# UI.net
KiCad netlist of a schematic drawn in Altium Designer
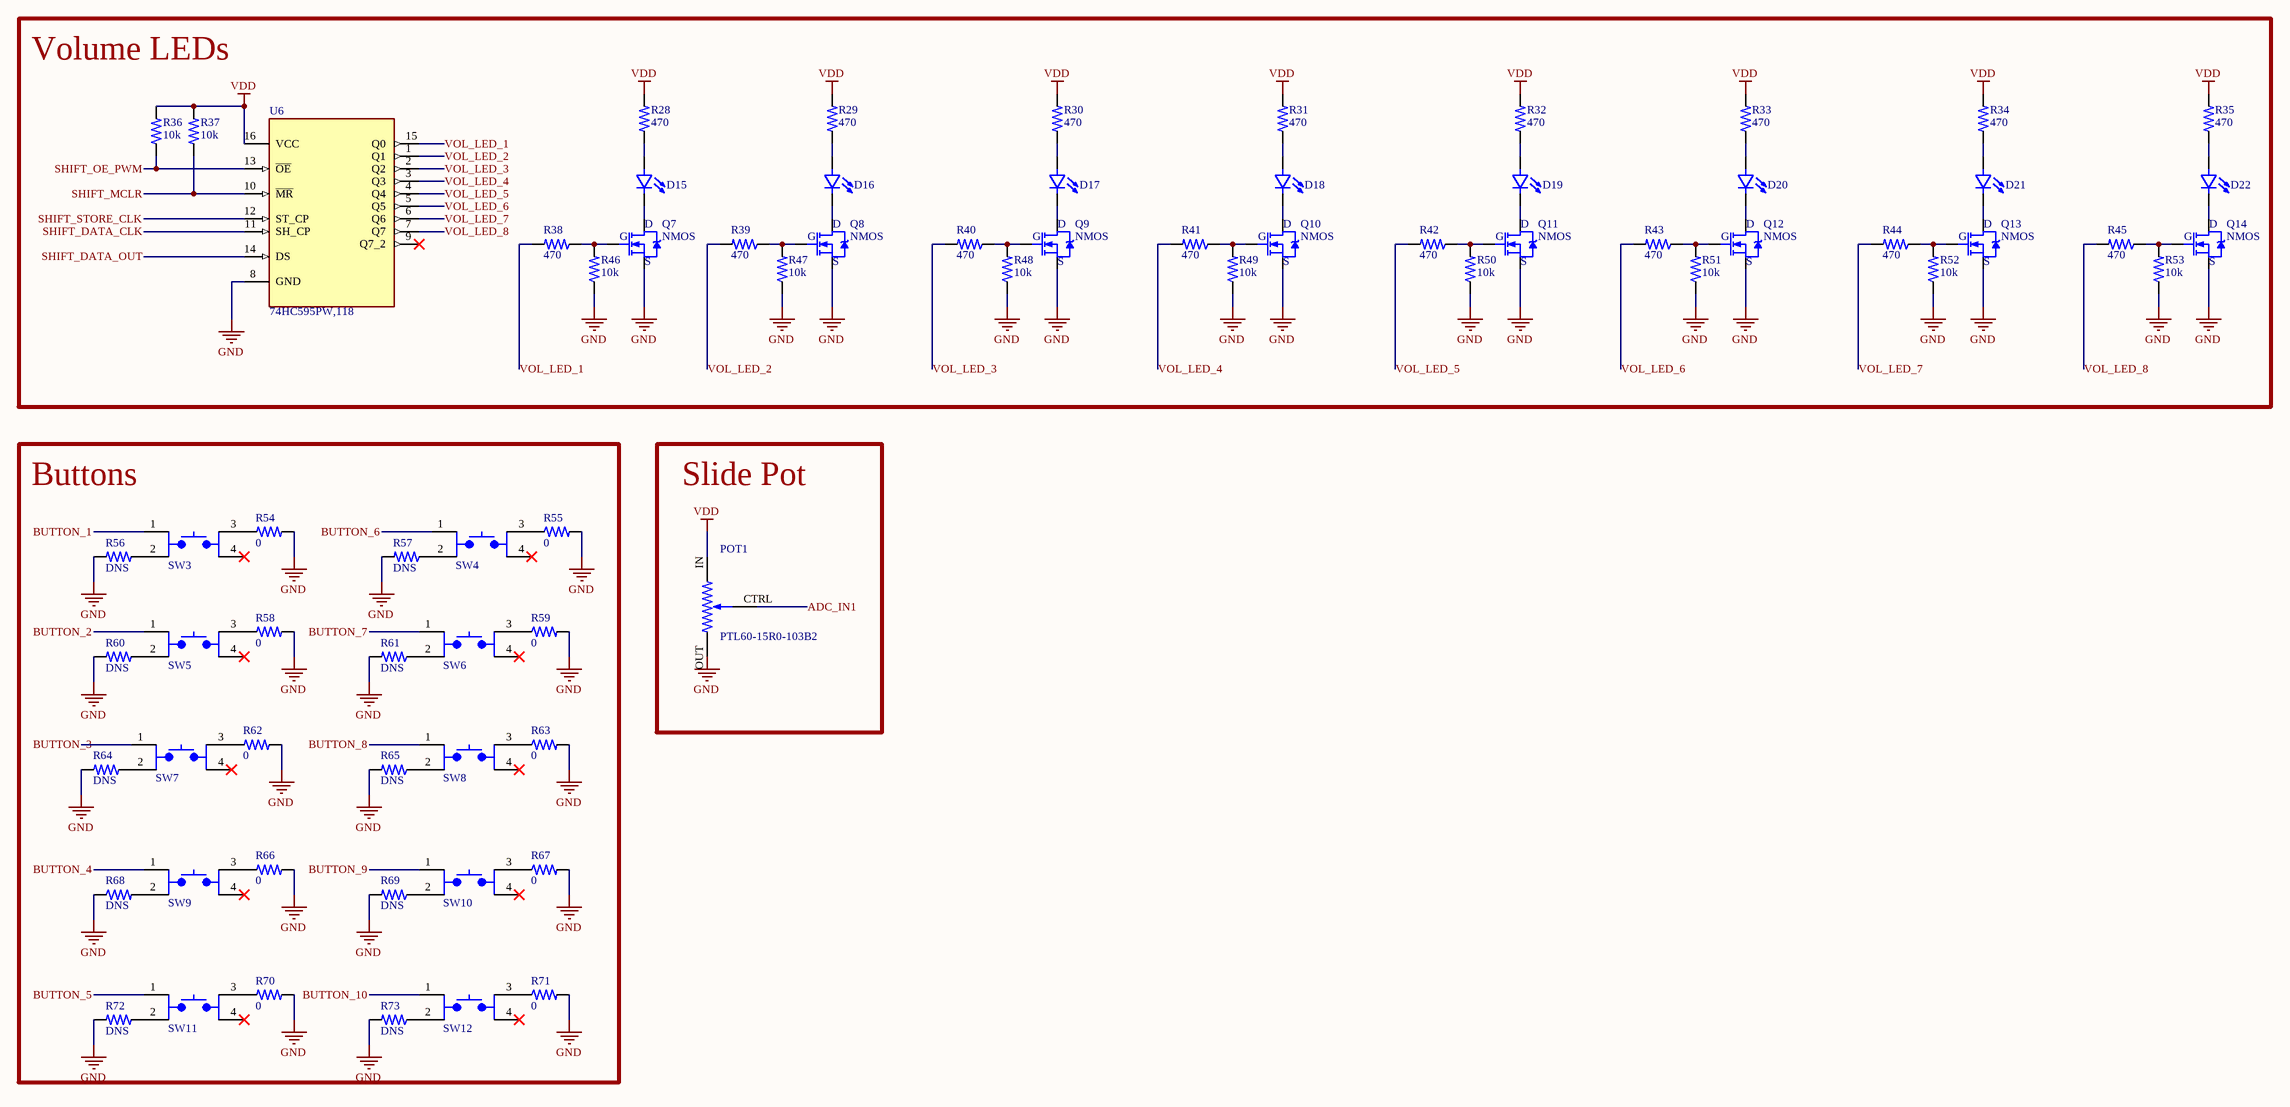
[diagram p0: UI.SchDoc]

(export (version "E")
  (design (tool "Eeschema 10.0.6"))
  (components
    (comp (ref "D15")
      (value "LED - single")
      (footprint "Christmas-2023_Soundboard:0603-LED")
      (description "LED")
      (fields (field (name "MFR") "Everlight Elec"))
      (libsource (lib "Christmas-2023_Soundboard") (part "LED - single"))
    )
    (comp (ref "D16")
      (value "LED - single")
      (footprint "Christmas-2023_Soundboard:0603-LED")
      (description "LED")
      (fields (field (name "MFR") "Hubei KENTO Elec"))
      (libsource (lib "Christmas-2023_Soundboard") (part "LED - single"))
    )
    (comp (ref "D17")
      (value "LED - single")
      (footprint "Christmas-2023_Soundboard:0603-LED")
      (description "LED")
      (fields (field (name "MFR") "Everlight Elec"))
      (libsource (lib "Christmas-2023_Soundboard") (part "LED - single"))
    )
    (comp (ref "D18")
      (value "LED - single")
      (footprint "Christmas-2023_Soundboard:0603-LED")
      (description "LED")
      (fields (field (name "MFR") "Hubei KENTO Elec"))
      (libsource (lib "Christmas-2023_Soundboard") (part "LED - single"))
    )
    (comp (ref "D19")
      (value "LED - single")
      (footprint "Christmas-2023_Soundboard:0603-LED")
      (description "LED")
      (fields (field (name "MFR") "Everlight Elec"))
      (libsource (lib "Christmas-2023_Soundboard") (part "LED - single"))
    )
    (comp (ref "D20")
      (value "LED - single")
      (footprint "Christmas-2023_Soundboard:0603-LED")
      (description "LED")
      (fields (field (name "MFR") "Hubei KENTO Elec"))
      (libsource (lib "Christmas-2023_Soundboard") (part "LED - single"))
    )
    (comp (ref "D21")
      (value "LED - single")
      (footprint "Christmas-2023_Soundboard:0603-LED")
      (description "LED")
      (fields (field (name "MFR") "Everlight Elec"))
      (libsource (lib "Christmas-2023_Soundboard") (part "LED - single"))
    )
    (comp (ref "D22")
      (value "LED - single")
      (footprint "Christmas-2023_Soundboard:0603-LED")
      (description "LED")
      (fields (field (name "MFR") "Hubei KENTO Elec"))
      (libsource (lib "Christmas-2023_Soundboard") (part "LED - single"))
    )
    (comp (ref "POT1")
      (value "PTL60-15R0-103B2")
      (footprint "Christmas-2023_Soundboard:BIG SLIDE POT")
      (description "POT 470 OHM 1/10W CARBON LINEAR")
      (fields (field (name "MFR") "Bourns Inc."))
      (libsource (lib "Christmas-2023_Soundboard") (part "POT"))
    )
    (comp (ref "Q7")
      (value "NMOS")
      (footprint "Christmas-2023_Soundboard:SOT-23")
      (description "N-Channel MOSFET")
      (fields (field (name "MFR") "Diodes Incorporated"))
      (libsource (lib "Christmas-2023_Soundboard") (part "NMOS"))
    )
    (comp (ref "Q8")
      (value "NMOS")
      (footprint "Christmas-2023_Soundboard:SOT-23")
      (description "N-Channel MOSFET")
      (fields (field (name "MFR") "Diodes Incorporated"))
      (libsource (lib "Christmas-2023_Soundboard") (part "NMOS"))
    )
    (comp (ref "Q9")
      (value "NMOS")
      (footprint "Christmas-2023_Soundboard:SOT-23")
      (description "N-Channel MOSFET")
      (fields (field (name "MFR") "Diodes Incorporated"))
      (libsource (lib "Christmas-2023_Soundboard") (part "NMOS"))
    )
    (comp (ref "Q10")
      (value "NMOS")
      (footprint "Christmas-2023_Soundboard:SOT-23")
      (description "N-Channel MOSFET")
      (fields (field (name "MFR") "Diodes Incorporated"))
      (libsource (lib "Christmas-2023_Soundboard") (part "NMOS"))
    )
    (comp (ref "Q11")
      (value "NMOS")
      (footprint "Christmas-2023_Soundboard:SOT-23")
      (description "N-Channel MOSFET")
      (fields (field (name "MFR") "Diodes Incorporated"))
      (libsource (lib "Christmas-2023_Soundboard") (part "NMOS"))
    )
    (comp (ref "Q12")
      (value "NMOS")
      (footprint "Christmas-2023_Soundboard:SOT-23")
      (description "N-Channel MOSFET")
      (fields (field (name "MFR") "Diodes Incorporated"))
      (libsource (lib "Christmas-2023_Soundboard") (part "NMOS"))
    )
    (comp (ref "Q13")
      (value "NMOS")
      (footprint "Christmas-2023_Soundboard:SOT-23")
      (description "N-Channel MOSFET")
      (fields (field (name "MFR") "Diodes Incorporated"))
      (libsource (lib "Christmas-2023_Soundboard") (part "NMOS"))
    )
    (comp (ref "Q14")
      (value "NMOS")
      (footprint "Christmas-2023_Soundboard:SOT-23")
      (description "N-Channel MOSFET")
      (fields (field (name "MFR") "Diodes Incorporated"))
      (libsource (lib "Christmas-2023_Soundboard") (part "NMOS"))
    )
    (comp (ref "R28")
      (value "470")
      (footprint "Christmas-2023_Soundboard:0603-RES")
      (description "Resistor")
      (fields (field (name "Comment") "RES"))
      (libsource (lib "Christmas-2023_Soundboard") (part "RES"))
    )
    (comp (ref "R29")
      (value "470")
      (footprint "Christmas-2023_Soundboard:0603-RES")
      (description "Resistor")
      (fields (field (name "Comment") "RES"))
      (libsource (lib "Christmas-2023_Soundboard") (part "RES"))
    )
    (comp (ref "R30")
      (value "470")
      (footprint "Christmas-2023_Soundboard:0603-RES")
      (description "Resistor")
      (fields (field (name "Comment") "RES"))
      (libsource (lib "Christmas-2023_Soundboard") (part "RES"))
    )
    (comp (ref "R31")
      (value "470")
      (footprint "Christmas-2023_Soundboard:0603-RES")
      (description "Resistor")
      (fields (field (name "Comment") "RES"))
      (libsource (lib "Christmas-2023_Soundboard") (part "RES"))
    )
    (comp (ref "R32")
      (value "470")
      (footprint "Christmas-2023_Soundboard:0603-RES")
      (description "Resistor")
      (fields (field (name "Comment") "RES"))
      (libsource (lib "Christmas-2023_Soundboard") (part "RES"))
    )
    (comp (ref "R33")
      (value "470")
      (footprint "Christmas-2023_Soundboard:0603-RES")
      (description "Resistor")
      (fields (field (name "Comment") "RES"))
      (libsource (lib "Christmas-2023_Soundboard") (part "RES"))
    )
    (comp (ref "R34")
      (value "470")
      (footprint "Christmas-2023_Soundboard:0603-RES")
      (description "Resistor")
      (fields (field (name "Comment") "RES"))
      (libsource (lib "Christmas-2023_Soundboard") (part "RES"))
    )
    (comp (ref "R35")
      (value "470")
      (footprint "Christmas-2023_Soundboard:0603-RES")
      (description "Resistor")
      (fields (field (name "Comment") "RES"))
      (libsource (lib "Christmas-2023_Soundboard") (part "RES"))
    )
    (comp (ref "R36")
      (value "10k")
      (footprint "Christmas-2023_Soundboard:0603-RES")
      (description "Resistor")
      (fields (field (name "Comment") "RES"))
      (libsource (lib "Christmas-2023_Soundboard") (part "RES"))
    )
    (comp (ref "R37")
      (value "10k")
      (footprint "Christmas-2023_Soundboard:0603-RES")
      (description "Resistor")
      (fields (field (name "Comment") "RES"))
      (libsource (lib "Christmas-2023_Soundboard") (part "RES"))
    )
    (comp (ref "R38")
      (value "470")
      (footprint "Christmas-2023_Soundboard:0603-RES")
      (description "Resistor")
      (fields (field (name "Comment") "RES"))
      (libsource (lib "Christmas-2023_Soundboard") (part "RES"))
    )
    (comp (ref "R39")
      (value "470")
      (footprint "Christmas-2023_Soundboard:0603-RES")
      (description "Resistor")
      (fields (field (name "Comment") "RES"))
      (libsource (lib "Christmas-2023_Soundboard") (part "RES"))
    )
    (comp (ref "R40")
      (value "470")
      (footprint "Christmas-2023_Soundboard:0603-RES")
      (description "Resistor")
      (fields (field (name "Comment") "RES"))
      (libsource (lib "Christmas-2023_Soundboard") (part "RES"))
    )
    (comp (ref "R41")
      (value "470")
      (footprint "Christmas-2023_Soundboard:0603-RES")
      (description "Resistor")
      (fields (field (name "Comment") "RES"))
      (libsource (lib "Christmas-2023_Soundboard") (part "RES"))
    )
    (comp (ref "R42")
      (value "470")
      (footprint "Christmas-2023_Soundboard:0603-RES")
      (description "Resistor")
      (fields (field (name "Comment") "RES"))
      (libsource (lib "Christmas-2023_Soundboard") (part "RES"))
    )
    (comp (ref "R43")
      (value "470")
      (footprint "Christmas-2023_Soundboard:0603-RES")
      (description "Resistor")
      (fields (field (name "Comment") "RES"))
      (libsource (lib "Christmas-2023_Soundboard") (part "RES"))
    )
    (comp (ref "R44")
      (value "470")
      (footprint "Christmas-2023_Soundboard:0603-RES")
      (description "Resistor")
      (fields (field (name "Comment") "RES"))
      (libsource (lib "Christmas-2023_Soundboard") (part "RES"))
    )
    (comp (ref "R45")
      (value "470")
      (footprint "Christmas-2023_Soundboard:0603-RES")
      (description "Resistor")
      (fields (field (name "Comment") "RES"))
      (libsource (lib "Christmas-2023_Soundboard") (part "RES"))
    )
    (comp (ref "R46")
      (value "10k")
      (footprint "Christmas-2023_Soundboard:0603-RES")
      (description "Resistor")
      (fields (field (name "Comment") "RES"))
      (libsource (lib "Christmas-2023_Soundboard") (part "RES"))
    )
    (comp (ref "R47")
      (value "10k")
      (footprint "Christmas-2023_Soundboard:0603-RES")
      (description "Resistor")
      (fields (field (name "Comment") "RES"))
      (libsource (lib "Christmas-2023_Soundboard") (part "RES"))
    )
    (comp (ref "R48")
      (value "10k")
      (footprint "Christmas-2023_Soundboard:0603-RES")
      (description "Resistor")
      (fields (field (name "Comment") "RES"))
      (libsource (lib "Christmas-2023_Soundboard") (part "RES"))
    )
    (comp (ref "R49")
      (value "10k")
      (footprint "Christmas-2023_Soundboard:0603-RES")
      (description "Resistor")
      (fields (field (name "Comment") "RES"))
      (libsource (lib "Christmas-2023_Soundboard") (part "RES"))
    )
    (comp (ref "R50")
      (value "10k")
      (footprint "Christmas-2023_Soundboard:0603-RES")
      (description "Resistor")
      (fields (field (name "Comment") "RES"))
      (libsource (lib "Christmas-2023_Soundboard") (part "RES"))
    )
    (comp (ref "R51")
      (value "10k")
      (footprint "Christmas-2023_Soundboard:0603-RES")
      (description "Resistor")
      (fields (field (name "Comment") "RES"))
      (libsource (lib "Christmas-2023_Soundboard") (part "RES"))
    )
    (comp (ref "R52")
      (value "10k")
      (footprint "Christmas-2023_Soundboard:0603-RES")
      (description "Resistor")
      (fields (field (name "Comment") "RES"))
      (libsource (lib "Christmas-2023_Soundboard") (part "RES"))
    )
    (comp (ref "R53")
      (value "10k")
      (footprint "Christmas-2023_Soundboard:0603-RES")
      (description "Resistor")
      (fields (field (name "Comment") "RES"))
      (libsource (lib "Christmas-2023_Soundboard") (part "RES"))
    )
    (comp (ref "R54")
      (value "0")
      (footprint "Christmas-2023_Soundboard:0603-RES")
      (description "Resistor")
      (fields (field (name "Comment") "RES"))
      (libsource (lib "Christmas-2023_Soundboard") (part "RES"))
    )
    (comp (ref "R55")
      (value "0")
      (footprint "Christmas-2023_Soundboard:0603-RES")
      (description "Resistor")
      (fields (field (name "Comment") "RES"))
      (libsource (lib "Christmas-2023_Soundboard") (part "RES"))
    )
    (comp (ref "R56")
      (value "DNS")
      (footprint "Christmas-2023_Soundboard:0603-RES")
      (description "Resistor")
      (fields (field (name "Comment") "RES"))
      (libsource (lib "Christmas-2023_Soundboard") (part "RES"))
    )
    (comp (ref "R57")
      (value "DNS")
      (footprint "Christmas-2023_Soundboard:0603-RES")
      (description "Resistor")
      (fields (field (name "Comment") "RES"))
      (libsource (lib "Christmas-2023_Soundboard") (part "RES"))
    )
    (comp (ref "R58")
      (value "0")
      (footprint "Christmas-2023_Soundboard:0603-RES")
      (description "Resistor")
      (fields (field (name "Comment") "RES"))
      (libsource (lib "Christmas-2023_Soundboard") (part "RES"))
    )
    (comp (ref "R59")
      (value "0")
      (footprint "Christmas-2023_Soundboard:0603-RES")
      (description "Resistor")
      (fields (field (name "Comment") "RES"))
      (libsource (lib "Christmas-2023_Soundboard") (part "RES"))
    )
    (comp (ref "R60")
      (value "DNS")
      (footprint "Christmas-2023_Soundboard:0603-RES")
      (description "Resistor")
      (fields (field (name "Comment") "RES"))
      (libsource (lib "Christmas-2023_Soundboard") (part "RES"))
    )
    (comp (ref "R61")
      (value "DNS")
      (footprint "Christmas-2023_Soundboard:0603-RES")
      (description "Resistor")
      (fields (field (name "Comment") "RES"))
      (libsource (lib "Christmas-2023_Soundboard") (part "RES"))
    )
    (comp (ref "R62")
      (value "0")
      (footprint "Christmas-2023_Soundboard:0603-RES")
      (description "Resistor")
      (fields (field (name "Comment") "RES"))
      (libsource (lib "Christmas-2023_Soundboard") (part "RES"))
    )
    (comp (ref "R63")
      (value "0")
      (footprint "Christmas-2023_Soundboard:0603-RES")
      (description "Resistor")
      (fields (field (name "Comment") "RES"))
      (libsource (lib "Christmas-2023_Soundboard") (part "RES"))
    )
    (comp (ref "R64")
      (value "DNS")
      (footprint "Christmas-2023_Soundboard:0603-RES")
      (description "Resistor")
      (fields (field (name "Comment") "RES"))
      (libsource (lib "Christmas-2023_Soundboard") (part "RES"))
    )
    (comp (ref "R65")
      (value "DNS")
      (footprint "Christmas-2023_Soundboard:0603-RES")
      (description "Resistor")
      (fields (field (name "Comment") "RES"))
      (libsource (lib "Christmas-2023_Soundboard") (part "RES"))
    )
    (comp (ref "R66")
      (value "0")
      (footprint "Christmas-2023_Soundboard:0603-RES")
      (description "Resistor")
      (fields (field (name "Comment") "RES"))
      (libsource (lib "Christmas-2023_Soundboard") (part "RES"))
    )
    (comp (ref "R67")
      (value "0")
      (footprint "Christmas-2023_Soundboard:0603-RES")
      (description "Resistor")
      (fields (field (name "Comment") "RES"))
      (libsource (lib "Christmas-2023_Soundboard") (part "RES"))
    )
    (comp (ref "R68")
      (value "DNS")
      (footprint "Christmas-2023_Soundboard:0603-RES")
      (description "Resistor")
      (fields (field (name "Comment") "RES"))
      (libsource (lib "Christmas-2023_Soundboard") (part "RES"))
    )
    (comp (ref "R69")
      (value "DNS")
      (footprint "Christmas-2023_Soundboard:0603-RES")
      (description "Resistor")
      (fields (field (name "Comment") "RES"))
      (libsource (lib "Christmas-2023_Soundboard") (part "RES"))
    )
    (comp (ref "R70")
      (value "0")
      (footprint "Christmas-2023_Soundboard:0603-RES")
      (description "Resistor")
      (fields (field (name "Comment") "RES"))
      (libsource (lib "Christmas-2023_Soundboard") (part "RES"))
    )
    (comp (ref "R71")
      (value "0")
      (footprint "Christmas-2023_Soundboard:0603-RES")
      (description "Resistor")
      (fields (field (name "Comment") "RES"))
      (libsource (lib "Christmas-2023_Soundboard") (part "RES"))
    )
    (comp (ref "R72")
      (value "DNS")
      (footprint "Christmas-2023_Soundboard:0603-RES")
      (description "Resistor")
      (fields (field (name "Comment") "RES"))
      (libsource (lib "Christmas-2023_Soundboard") (part "RES"))
    )
    (comp (ref "R73")
      (value "DNS")
      (footprint "Christmas-2023_Soundboard:0603-RES")
      (description "Resistor")
      (fields (field (name "Comment") "RES"))
      (libsource (lib "Christmas-2023_Soundboard") (part "RES"))
    )
    (comp (ref "SW3")
      (value "SPDT SMT Tactile Push Button Switch")
      (footprint "Christmas-2023_Soundboard:TACTILE SWITCH")
      (fields (field (name "MFR") "TE Connectivity ALCOSWITCH Switches"))
      (libsource (lib "Christmas-2023_Soundboard") (part "SPDT SMT Tactile Push Button Switch"))
    )
    (comp (ref "SW4")
      (value "SPDT SMT Tactile Push Button Switch")
      (footprint "Christmas-2023_Soundboard:TACTILE SWITCH")
      (fields (field (name "MFR") "TE Connectivity ALCOSWITCH Switches"))
      (libsource (lib "Christmas-2023_Soundboard") (part "SPDT SMT Tactile Push Button Switch"))
    )
    (comp (ref "SW5")
      (value "SPDT SMT Tactile Push Button Switch")
      (footprint "Christmas-2023_Soundboard:TACTILE SWITCH")
      (fields (field (name "MFR") "TE Connectivity ALCOSWITCH Switches"))
      (libsource (lib "Christmas-2023_Soundboard") (part "SPDT SMT Tactile Push Button Switch"))
    )
    (comp (ref "SW6")
      (value "SPDT SMT Tactile Push Button Switch")
      (footprint "Christmas-2023_Soundboard:TACTILE SWITCH")
      (fields (field (name "MFR") "TE Connectivity ALCOSWITCH Switches"))
      (libsource (lib "Christmas-2023_Soundboard") (part "SPDT SMT Tactile Push Button Switch"))
    )
    (comp (ref "SW7")
      (value "SPDT SMT Tactile Push Button Switch")
      (footprint "Christmas-2023_Soundboard:TACTILE SWITCH")
      (fields (field (name "MFR") "TE Connectivity ALCOSWITCH Switches"))
      (libsource (lib "Christmas-2023_Soundboard") (part "SPDT SMT Tactile Push Button Switch"))
    )
    (comp (ref "SW8")
      (value "SPDT SMT Tactile Push Button Switch")
      (footprint "Christmas-2023_Soundboard:TACTILE SWITCH")
      (fields (field (name "MFR") "TE Connectivity ALCOSWITCH Switches"))
      (libsource (lib "Christmas-2023_Soundboard") (part "SPDT SMT Tactile Push Button Switch"))
    )
    (comp (ref "SW9")
      (value "SPDT SMT Tactile Push Button Switch")
      (footprint "Christmas-2023_Soundboard:TACTILE SWITCH")
      (fields (field (name "MFR") "TE Connectivity ALCOSWITCH Switches"))
      (libsource (lib "Christmas-2023_Soundboard") (part "SPDT SMT Tactile Push Button Switch"))
    )
    (comp (ref "SW10")
      (value "SPDT SMT Tactile Push Button Switch")
      (footprint "Christmas-2023_Soundboard:TACTILE SWITCH")
      (fields (field (name "MFR") "TE Connectivity ALCOSWITCH Switches"))
      (libsource (lib "Christmas-2023_Soundboard") (part "SPDT SMT Tactile Push Button Switch"))
    )
    (comp (ref "SW11")
      (value "SPDT SMT Tactile Push Button Switch")
      (footprint "Christmas-2023_Soundboard:TACTILE SWITCH")
      (fields (field (name "MFR") "TE Connectivity ALCOSWITCH Switches"))
      (libsource (lib "Christmas-2023_Soundboard") (part "SPDT SMT Tactile Push Button Switch"))
    )
    (comp (ref "SW12")
      (value "SPDT SMT Tactile Push Button Switch")
      (footprint "Christmas-2023_Soundboard:TACTILE SWITCH")
      (fields (field (name "MFR") "TE Connectivity ALCOSWITCH Switches"))
      (libsource (lib "Christmas-2023_Soundboard") (part "SPDT SMT Tactile Push Button Switch"))
    )
    (comp (ref "U6")
      (value "74HC595PW,118")
      (footprint "Christmas-2023_Soundboard:16-TSSOP")
      (description "Shift Shift Register 1 Element 8 Bit 16-TSSOP")
      (fields (field (name "MFR") "Nexperia USA Inc."))
      (libsource (lib "Christmas-2023_Soundboard") (part "SHIFT REGISTER 8 BIT"))
    )
  )
  (nets
    (net (code "1") (name "/ADC_IN1") (class "Default")
      (node (ref "POT1") (pin "CTRL") (pinfunction "WIPER_CTRL") (pintype "passive"))
    )
    (net (code "2") (name "/BUTTON_1") (class "Default")
      (node (ref "SW3") (pin "1") (pinfunction "1_1") (pintype "passive"))
    )
    (net (code "3") (name "/BUTTON_2") (class "Default")
      (node (ref "SW5") (pin "1") (pinfunction "1_1") (pintype "passive"))
    )
    (net (code "4") (name "/BUTTON_3") (class "Default")
      (node (ref "SW7") (pin "1") (pinfunction "1_1") (pintype "passive"))
    )
    (net (code "5") (name "/BUTTON_4") (class "Default")
      (node (ref "SW9") (pin "1") (pinfunction "1_1") (pintype "passive"))
    )
    (net (code "6") (name "/BUTTON_5") (class "Default")
      (node (ref "SW11") (pin "1") (pinfunction "1_1") (pintype "passive"))
    )
    (net (code "7") (name "/BUTTON_6") (class "Default")
      (node (ref "SW4") (pin "1") (pinfunction "1_1") (pintype "passive"))
    )
    (net (code "8") (name "/BUTTON_7") (class "Default")
      (node (ref "SW6") (pin "1") (pinfunction "1_1") (pintype "passive"))
    )
    (net (code "9") (name "/BUTTON_8") (class "Default")
      (node (ref "SW8") (pin "1") (pinfunction "1_1") (pintype "passive"))
    )
    (net (code "10") (name "/BUTTON_9") (class "Default")
      (node (ref "SW10") (pin "1") (pinfunction "1_1") (pintype "passive"))
    )
    (net (code "11") (name "/BUTTON_10") (class "Default")
      (node (ref "SW12") (pin "1") (pinfunction "1_1") (pintype "passive"))
    )
    (net (code "12") (name "/SHIFT_DATA_CLK") (class "Default")
      (node (ref "U6") (pin "11") (pinfunction "SH_CP_11") (pintype "input"))
    )
    (net (code "13") (name "/SHIFT_DATA_OUT") (class "Default")
      (node (ref "U6") (pin "14") (pinfunction "DS_14") (pintype "input"))
    )
    (net (code "14") (name "/SHIFT_MCLR") (class "Default")
      (node (ref "R37") (pin "1") (pinfunction "1_1") (pintype "passive"))
      (node (ref "U6") (pin "10") (pinfunction "~{MR}_10") (pintype "input"))
    )
    (net (code "15") (name "/SHIFT_OE_PWM") (class "Default")
      (node (ref "R36") (pin "1") (pinfunction "1_1") (pintype "passive"))
      (node (ref "U6") (pin "13") (pinfunction "~{OE}_13") (pintype "input"))
    )
    (net (code "16") (name "/SHIFT_STORE_CLK") (class "Default")
      (node (ref "U6") (pin "12") (pinfunction "ST_CP_12") (pintype "input"))
    )
    (net (code "17") (name "/VOL_LED_1") (class "Default")
      (node (ref "R38") (pin "2") (pinfunction "2_2") (pintype "passive"))
      (node (ref "U6") (pin "15") (pinfunction "Q0_15") (pintype "output"))
    )
    (net (code "18") (name "/VOL_LED_2") (class "Default")
      (node (ref "R39") (pin "2") (pinfunction "2_2") (pintype "passive"))
      (node (ref "U6") (pin "1") (pinfunction "Q1_1") (pintype "output"))
    )
    (net (code "19") (name "/VOL_LED_3") (class "Default")
      (node (ref "R40") (pin "2") (pinfunction "2_2") (pintype "passive"))
      (node (ref "U6") (pin "2") (pinfunction "Q2_2") (pintype "output"))
    )
    (net (code "20") (name "/VOL_LED_4") (class "Default")
      (node (ref "R41") (pin "2") (pinfunction "2_2") (pintype "passive"))
      (node (ref "U6") (pin "3") (pinfunction "Q3_3") (pintype "output"))
    )
    (net (code "21") (name "/VOL_LED_5") (class "Default")
      (node (ref "R42") (pin "2") (pinfunction "2_2") (pintype "passive"))
      (node (ref "U6") (pin "4") (pinfunction "Q4_4") (pintype "output"))
    )
    (net (code "22") (name "/VOL_LED_6") (class "Default")
      (node (ref "R43") (pin "2") (pinfunction "2_2") (pintype "passive"))
      (node (ref "U6") (pin "5") (pinfunction "Q5_5") (pintype "output"))
    )
    (net (code "23") (name "/VOL_LED_7") (class "Default")
      (node (ref "R44") (pin "2") (pinfunction "2_2") (pintype "passive"))
      (node (ref "U6") (pin "6") (pinfunction "Q6_6") (pintype "output"))
    )
    (net (code "24") (name "/VOL_LED_8") (class "Default")
      (node (ref "R45") (pin "2") (pinfunction "2_2") (pintype "passive"))
      (node (ref "U6") (pin "7") (pinfunction "Q7_7") (pintype "output"))
    )
    (net (code "25") (name "GND") (class "Default")
      (node (ref "POT1") (pin "OUT") (pinfunction "FINAL_OUT") (pintype "passive"))
      (node (ref "Q10") (pin "2") (pinfunction "S_2") (pintype "passive"))
      (node (ref "Q11") (pin "2") (pinfunction "S_2") (pintype "passive"))
      (node (ref "Q12") (pin "2") (pinfunction "S_2") (pintype "passive"))
      (node (ref "Q13") (pin "2") (pinfunction "S_2") (pintype "passive"))
      (node (ref "Q14") (pin "2") (pinfunction "S_2") (pintype "passive"))
      (node (ref "Q7") (pin "2") (pinfunction "S_2") (pintype "passive"))
      (node (ref "Q8") (pin "2") (pinfunction "S_2") (pintype "passive"))
      (node (ref "Q9") (pin "2") (pinfunction "S_2") (pintype "passive"))
      (node (ref "R46") (pin "1") (pinfunction "1_1") (pintype "passive"))
      (node (ref "R47") (pin "1") (pinfunction "1_1") (pintype "passive"))
      (node (ref "R48") (pin "1") (pinfunction "1_1") (pintype "passive"))
      (node (ref "R49") (pin "1") (pinfunction "1_1") (pintype "passive"))
      (node (ref "R50") (pin "1") (pinfunction "1_1") (pintype "passive"))
      (node (ref "R51") (pin "1") (pinfunction "1_1") (pintype "passive"))
      (node (ref "R52") (pin "1") (pinfunction "1_1") (pintype "passive"))
      (node (ref "R53") (pin "1") (pinfunction "1_1") (pintype "passive"))
      (node (ref "R54") (pin "2") (pinfunction "2_2") (pintype "passive"))
      (node (ref "R55") (pin "2") (pinfunction "2_2") (pintype "passive"))
      (node (ref "R56") (pin "2") (pinfunction "2_2") (pintype "passive"))
      (node (ref "R57") (pin "2") (pinfunction "2_2") (pintype "passive"))
      (node (ref "R58") (pin "2") (pinfunction "2_2") (pintype "passive"))
      (node (ref "R59") (pin "2") (pinfunction "2_2") (pintype "passive"))
      (node (ref "R60") (pin "2") (pinfunction "2_2") (pintype "passive"))
      (node (ref "R61") (pin "2") (pinfunction "2_2") (pintype "passive"))
      (node (ref "R62") (pin "2") (pinfunction "2_2") (pintype "passive"))
      (node (ref "R63") (pin "2") (pinfunction "2_2") (pintype "passive"))
      (node (ref "R64") (pin "2") (pinfunction "2_2") (pintype "passive"))
      (node (ref "R65") (pin "2") (pinfunction "2_2") (pintype "passive"))
      (node (ref "R66") (pin "2") (pinfunction "2_2") (pintype "passive"))
      (node (ref "R67") (pin "2") (pinfunction "2_2") (pintype "passive"))
      (node (ref "R68") (pin "1") (pinfunction "1_1") (pintype "passive"))
      (node (ref "R69") (pin "2") (pinfunction "2_2") (pintype "passive"))
      (node (ref "R70") (pin "2") (pinfunction "2_2") (pintype "passive"))
      (node (ref "R71") (pin "2") (pinfunction "2_2") (pintype "passive"))
      (node (ref "R72") (pin "2") (pinfunction "2_2") (pintype "passive"))
      (node (ref "R73") (pin "2") (pinfunction "2_2") (pintype "passive"))
      (node (ref "U6") (pin "8") (pinfunction "GND_8") (pintype "passive"))
    )
    (net (code "26") (name "Net-(D15-A)") (class "Default")
      (node (ref "D15") (pin "1") (pinfunction "A_1") (pintype "passive"))
      (node (ref "R28") (pin "1") (pinfunction "1_1") (pintype "passive"))
    )
    (net (code "27") (name "Net-(D15-C)") (class "Default")
      (node (ref "D15") (pin "2") (pinfunction "C_2") (pintype "passive"))
      (node (ref "Q7") (pin "3") (pinfunction "D_3") (pintype "passive"))
    )
    (net (code "28") (name "Net-(D16-A)") (class "Default")
      (node (ref "D16") (pin "1") (pinfunction "A_1") (pintype "passive"))
      (node (ref "R29") (pin "1") (pinfunction "1_1") (pintype "passive"))
    )
    (net (code "29") (name "Net-(D16-C)") (class "Default")
      (node (ref "D16") (pin "2") (pinfunction "C_2") (pintype "passive"))
      (node (ref "Q8") (pin "3") (pinfunction "D_3") (pintype "passive"))
    )
    (net (code "30") (name "Net-(D17-A)") (class "Default")
      (node (ref "D17") (pin "1") (pinfunction "A_1") (pintype "passive"))
      (node (ref "R30") (pin "1") (pinfunction "1_1") (pintype "passive"))
    )
    (net (code "31") (name "Net-(D17-C)") (class "Default")
      (node (ref "D17") (pin "2") (pinfunction "C_2") (pintype "passive"))
      (node (ref "Q9") (pin "3") (pinfunction "D_3") (pintype "passive"))
    )
    (net (code "32") (name "Net-(D18-A)") (class "Default")
      (node (ref "D18") (pin "1") (pinfunction "A_1") (pintype "passive"))
      (node (ref "R31") (pin "1") (pinfunction "1_1") (pintype "passive"))
    )
    (net (code "33") (name "Net-(D18-C)") (class "Default")
      (node (ref "D18") (pin "2") (pinfunction "C_2") (pintype "passive"))
      (node (ref "Q10") (pin "3") (pinfunction "D_3") (pintype "passive"))
    )
    (net (code "34") (name "Net-(D19-A)") (class "Default")
      (node (ref "D19") (pin "1") (pinfunction "A_1") (pintype "passive"))
      (node (ref "R32") (pin "1") (pinfunction "1_1") (pintype "passive"))
    )
    (net (code "35") (name "Net-(D19-C)") (class "Default")
      (node (ref "D19") (pin "2") (pinfunction "C_2") (pintype "passive"))
      (node (ref "Q11") (pin "3") (pinfunction "D_3") (pintype "passive"))
    )
    (net (code "36") (name "Net-(D20-A)") (class "Default")
      (node (ref "D20") (pin "1") (pinfunction "A_1") (pintype "passive"))
      (node (ref "R33") (pin "1") (pinfunction "1_1") (pintype "passive"))
    )
    (net (code "37") (name "Net-(D20-C)") (class "Default")
      (node (ref "D20") (pin "2") (pinfunction "C_2") (pintype "passive"))
      (node (ref "Q12") (pin "3") (pinfunction "D_3") (pintype "passive"))
    )
    (net (code "38") (name "Net-(D21-A)") (class "Default")
      (node (ref "D21") (pin "1") (pinfunction "A_1") (pintype "passive"))
      (node (ref "R34") (pin "1") (pinfunction "1_1") (pintype "passive"))
    )
    (net (code "39") (name "Net-(D21-C)") (class "Default")
      (node (ref "D21") (pin "2") (pinfunction "C_2") (pintype "passive"))
      (node (ref "Q13") (pin "3") (pinfunction "D_3") (pintype "passive"))
    )
    (net (code "40") (name "Net-(D22-A)") (class "Default")
      (node (ref "D22") (pin "1") (pinfunction "A_1") (pintype "passive"))
      (node (ref "R35") (pin "1") (pinfunction "1_1") (pintype "passive"))
    )
    (net (code "41") (name "Net-(D22-C)") (class "Default")
      (node (ref "D22") (pin "2") (pinfunction "C_2") (pintype "passive"))
      (node (ref "Q14") (pin "3") (pinfunction "D_3") (pintype "passive"))
    )
    (net (code "42") (name "Net-(Q7-G)") (class "Default")
      (node (ref "Q7") (pin "1") (pinfunction "G_1") (pintype "passive"))
      (node (ref "R38") (pin "1") (pinfunction "1_1") (pintype "passive"))
      (node (ref "R46") (pin "2") (pinfunction "2_2") (pintype "passive"))
    )
    (net (code "43") (name "Net-(Q8-G)") (class "Default")
      (node (ref "Q8") (pin "1") (pinfunction "G_1") (pintype "passive"))
      (node (ref "R39") (pin "1") (pinfunction "1_1") (pintype "passive"))
      (node (ref "R47") (pin "2") (pinfunction "2_2") (pintype "passive"))
    )
    (net (code "44") (name "Net-(Q9-G)") (class "Default")
      (node (ref "Q9") (pin "1") (pinfunction "G_1") (pintype "passive"))
      (node (ref "R40") (pin "1") (pinfunction "1_1") (pintype "passive"))
      (node (ref "R48") (pin "2") (pinfunction "2_2") (pintype "passive"))
    )
    (net (code "45") (name "Net-(Q10-G)") (class "Default")
      (node (ref "Q10") (pin "1") (pinfunction "G_1") (pintype "passive"))
      (node (ref "R41") (pin "1") (pinfunction "1_1") (pintype "passive"))
      (node (ref "R49") (pin "2") (pinfunction "2_2") (pintype "passive"))
    )
    (net (code "46") (name "Net-(Q11-G)") (class "Default")
      (node (ref "Q11") (pin "1") (pinfunction "G_1") (pintype "passive"))
      (node (ref "R42") (pin "1") (pinfunction "1_1") (pintype "passive"))
      (node (ref "R50") (pin "2") (pinfunction "2_2") (pintype "passive"))
    )
    (net (code "47") (name "Net-(Q12-G)") (class "Default")
      (node (ref "Q12") (pin "1") (pinfunction "G_1") (pintype "passive"))
      (node (ref "R43") (pin "1") (pinfunction "1_1") (pintype "passive"))
      (node (ref "R51") (pin "2") (pinfunction "2_2") (pintype "passive"))
    )
    (net (code "48") (name "Net-(Q13-G)") (class "Default")
      (node (ref "Q13") (pin "1") (pinfunction "G_1") (pintype "passive"))
      (node (ref "R44") (pin "1") (pinfunction "1_1") (pintype "passive"))
      (node (ref "R52") (pin "2") (pinfunction "2_2") (pintype "passive"))
    )
    (net (code "49") (name "Net-(Q14-G)") (class "Default")
      (node (ref "Q14") (pin "1") (pinfunction "G_1") (pintype "passive"))
      (node (ref "R45") (pin "1") (pinfunction "1_1") (pintype "passive"))
      (node (ref "R53") (pin "2") (pinfunction "2_2") (pintype "passive"))
    )
    (net (code "50") (name "Net-(R54-Pad1)") (class "Default")
      (node (ref "R54") (pin "1") (pinfunction "1_1") (pintype "passive"))
      (node (ref "SW3") (pin "3") (pinfunction "3_3") (pintype "passive"))
    )
    (net (code "51") (name "Net-(R55-Pad1)") (class "Default")
      (node (ref "R55") (pin "1") (pinfunction "1_1") (pintype "passive"))
      (node (ref "SW4") (pin "3") (pinfunction "3_3") (pintype "passive"))
    )
    (net (code "52") (name "Net-(R56-Pad1)") (class "Default")
      (node (ref "R56") (pin "1") (pinfunction "1_1") (pintype "passive"))
      (node (ref "SW3") (pin "2") (pinfunction "2_2") (pintype "passive"))
    )
    (net (code "53") (name "Net-(R57-Pad1)") (class "Default")
      (node (ref "R57") (pin "1") (pinfunction "1_1") (pintype "passive"))
      (node (ref "SW4") (pin "2") (pinfunction "2_2") (pintype "passive"))
    )
    (net (code "54") (name "Net-(R58-Pad1)") (class "Default")
      (node (ref "R58") (pin "1") (pinfunction "1_1") (pintype "passive"))
      (node (ref "SW5") (pin "3") (pinfunction "3_3") (pintype "passive"))
    )
    (net (code "55") (name "Net-(R59-Pad1)") (class "Default")
      (node (ref "R59") (pin "1") (pinfunction "1_1") (pintype "passive"))
      (node (ref "SW6") (pin "3") (pinfunction "3_3") (pintype "passive"))
    )
    (net (code "56") (name "Net-(R60-Pad1)") (class "Default")
      (node (ref "R60") (pin "1") (pinfunction "1_1") (pintype "passive"))
      (node (ref "SW5") (pin "2") (pinfunction "2_2") (pintype "passive"))
    )
    (net (code "57") (name "Net-(R61-Pad1)") (class "Default")
      (node (ref "R61") (pin "1") (pinfunction "1_1") (pintype "passive"))
      (node (ref "SW6") (pin "2") (pinfunction "2_2") (pintype "passive"))
    )
    (net (code "58") (name "Net-(R62-Pad1)") (class "Default")
      (node (ref "R62") (pin "1") (pinfunction "1_1") (pintype "passive"))
      (node (ref "SW7") (pin "3") (pinfunction "3_3") (pintype "passive"))
    )
    (net (code "59") (name "Net-(R63-Pad1)") (class "Default")
      (node (ref "R63") (pin "1") (pinfunction "1_1") (pintype "passive"))
      (node (ref "SW8") (pin "3") (pinfunction "3_3") (pintype "passive"))
    )
    (net (code "60") (name "Net-(R64-Pad1)") (class "Default")
      (node (ref "R64") (pin "1") (pinfunction "1_1") (pintype "passive"))
      (node (ref "SW7") (pin "2") (pinfunction "2_2") (pintype "passive"))
    )
    (net (code "61") (name "Net-(R65-Pad1)") (class "Default")
      (node (ref "R65") (pin "1") (pinfunction "1_1") (pintype "passive"))
      (node (ref "SW8") (pin "2") (pinfunction "2_2") (pintype "passive"))
    )
    (net (code "62") (name "Net-(R66-Pad1)") (class "Default")
      (node (ref "R66") (pin "1") (pinfunction "1_1") (pintype "passive"))
      (node (ref "SW9") (pin "3") (pinfunction "3_3") (pintype "passive"))
    )
    (net (code "63") (name "Net-(R67-Pad1)") (class "Default")
      (node (ref "R67") (pin "1") (pinfunction "1_1") (pintype "passive"))
      (node (ref "SW10") (pin "3") (pinfunction "3_3") (pintype "passive"))
    )
    (net (code "64") (name "Net-(R68-Pad2)") (class "Default")
      (node (ref "R68") (pin "2") (pinfunction "2_2") (pintype "passive"))
      (node (ref "SW9") (pin "2") (pinfunction "2_2") (pintype "passive"))
    )
    (net (code "65") (name "Net-(R69-Pad1)") (class "Default")
      (node (ref "R69") (pin "1") (pinfunction "1_1") (pintype "passive"))
      (node (ref "SW10") (pin "2") (pinfunction "2_2") (pintype "passive"))
    )
    (net (code "66") (name "Net-(R70-Pad1)") (class "Default")
      (node (ref "R70") (pin "1") (pinfunction "1_1") (pintype "passive"))
      (node (ref "SW11") (pin "3") (pinfunction "3_3") (pintype "passive"))
    )
    (net (code "67") (name "Net-(R71-Pad1)") (class "Default")
      (node (ref "R71") (pin "1") (pinfunction "1_1") (pintype "passive"))
      (node (ref "SW12") (pin "3") (pinfunction "3_3") (pintype "passive"))
    )
    (net (code "68") (name "Net-(R72-Pad1)") (class "Default")
      (node (ref "R72") (pin "1") (pinfunction "1_1") (pintype "passive"))
      (node (ref "SW11") (pin "2") (pinfunction "2_2") (pintype "passive"))
    )
    (net (code "69") (name "Net-(R73-Pad1)") (class "Default")
      (node (ref "R73") (pin "1") (pinfunction "1_1") (pintype "passive"))
      (node (ref "SW12") (pin "2") (pinfunction "2_2") (pintype "passive"))
    )
    (net (code "70") (name "VDD") (class "Default")
      (node (ref "POT1") (pin "IN") (pinfunction "INITIAL_IN") (pintype "passive"))
      (node (ref "R28") (pin "2") (pinfunction "2_2") (pintype "passive"))
      (node (ref "R29") (pin "2") (pinfunction "2_2") (pintype "passive"))
      (node (ref "R30") (pin "2") (pinfunction "2_2") (pintype "passive"))
      (node (ref "R31") (pin "2") (pinfunction "2_2") (pintype "passive"))
      (node (ref "R32") (pin "2") (pinfunction "2_2") (pintype "passive"))
      (node (ref "R33") (pin "2") (pinfunction "2_2") (pintype "passive"))
      (node (ref "R34") (pin "2") (pinfunction "2_2") (pintype "passive"))
      (node (ref "R35") (pin "2") (pinfunction "2_2") (pintype "passive"))
      (node (ref "R36") (pin "2") (pinfunction "2_2") (pintype "passive"))
      (node (ref "R37") (pin "2") (pinfunction "2_2") (pintype "passive"))
      (node (ref "U6") (pin "16") (pinfunction "VCC_16") (pintype "power_in"))
    )
    (net (code "71") (name "unconnected-(SW3-Pad4)") (class "Default")
      (node (ref "SW3") (pin "4") (pinfunction "4_4") (pintype "passive+no_connect"))
    )
    (net (code "72") (name "unconnected-(SW4-Pad4)") (class "Default")
      (node (ref "SW4") (pin "4") (pinfunction "4_4") (pintype "passive+no_connect"))
    )
    (net (code "73") (name "unconnected-(SW5-Pad4)") (class "Default")
      (node (ref "SW5") (pin "4") (pinfunction "4_4") (pintype "passive+no_connect"))
    )
    (net (code "74") (name "unconnected-(SW6-Pad4)") (class "Default")
      (node (ref "SW6") (pin "4") (pinfunction "4_4") (pintype "passive+no_connect"))
    )
    (net (code "75") (name "unconnected-(SW7-Pad4)") (class "Default")
      (node (ref "SW7") (pin "4") (pinfunction "4_4") (pintype "passive+no_connect"))
    )
    (net (code "76") (name "unconnected-(SW8-Pad4)") (class "Default")
      (node (ref "SW8") (pin "4") (pinfunction "4_4") (pintype "passive+no_connect"))
    )
    (net (code "77") (name "unconnected-(SW9-Pad4)") (class "Default")
      (node (ref "SW9") (pin "4") (pinfunction "4_4") (pintype "passive+no_connect"))
    )
    (net (code "78") (name "unconnected-(SW10-Pad4)") (class "Default")
      (node (ref "SW10") (pin "4") (pinfunction "4_4") (pintype "passive+no_connect"))
    )
    (net (code "79") (name "unconnected-(SW11-Pad4)") (class "Default")
      (node (ref "SW11") (pin "4") (pinfunction "4_4") (pintype "passive+no_connect"))
    )
    (net (code "80") (name "unconnected-(SW12-Pad4)") (class "Default")
      (node (ref "SW12") (pin "4") (pinfunction "4_4") (pintype "passive+no_connect"))
    )
    (net (code "81") (name "unconnected-(U6-Q7_2-Pad9)") (class "Default")
      (node (ref "U6") (pin "9") (pinfunction "Q7_2_9") (pintype "output+no_connect"))
    )
  )
)
